# Fans.net
KiCad netlist of a schematic drawn in Altium Designer
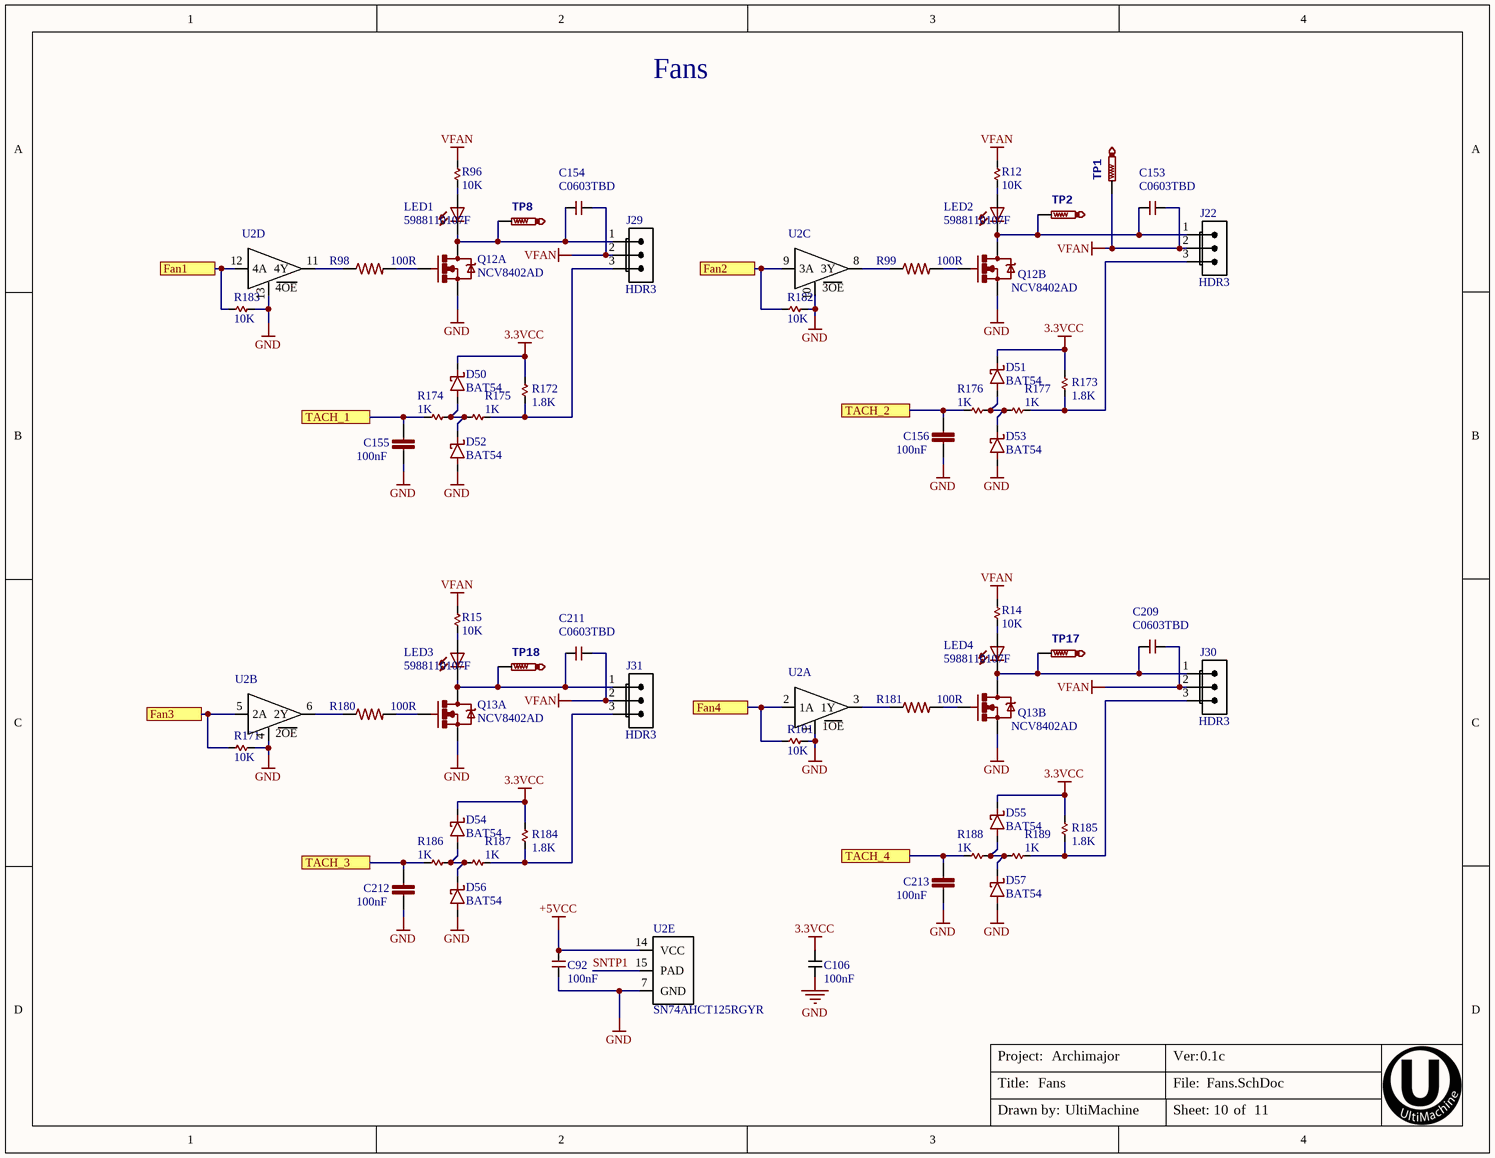
[diagram p0: Fans.SchDoc]

(export (version "E")
  (design (tool "Eeschema 10.0.6"))
  (components
    (comp (ref "C92")
      (value "100nF")
      (footprint "C0402")
      (description "CAP CER 0402 100nF 16V 10% X7R")
      (fields (field (name "MANUFACTURER") "Murata") (field (name "PART") "GRM155R71C104KA88D"))
      (libsource (lib "Capacitors") (part "100nF 0402 16V X7R"))
    )
    (comp (ref "C106")
      (value "100nF")
      (footprint "C0201 Large Pads")
      (description "CAP CER 0.1UF 6.3V 10% X5R 0201")
      (fields (field (name "PART") "CL03A104KQ3NNNC") (field (name "MANUFACTURER") "Samsung"))
      (libsource (lib "Capacitors") (part "100nF 6.3V X5R 0201"))
    )
    (comp (ref "C153")
      (value "C0603TBD")
      (footprint "C0603")
      (description "Capacitor Non Polarized")
      (fields (field (name "PART") "DNI-C0603TBD"))
      (libsource (lib "Capacitors") (part "C0603TBD"))
    )
    (comp (ref "C154")
      (value "C0603TBD")
      (footprint "C0603")
      (description "Capacitor Non Polarized")
      (fields (field (name "PART") "DNI-C0603TBD"))
      (libsource (lib "Capacitors") (part "C0603TBD"))
    )
    (comp (ref "C155")
      (value "100nF")
      (footprint "C0402")
      (description "CAP CER 0402 100nF 16V 10% X7R")
      (fields (field (name "MANUFACTURER") "Murata") (field (name "PART") "GRM155R71C104KA88D"))
      (libsource (lib "3Delight") (part "GRM155R71C104KA88D"))
    )
    (comp (ref "C156")
      (value "100nF")
      (footprint "C0402")
      (description "CAP CER 0402 100nF 16V 10% X7R")
      (fields (field (name "MANUFACTURER") "Murata") (field (name "PART") "GRM155R71C104KA88D"))
      (libsource (lib "3Delight") (part "GRM155R71C104KA88D"))
    )
    (comp (ref "C209")
      (value "C0603TBD")
      (footprint "C0603")
      (description "Capacitor Non Polarized")
      (fields (field (name "PART") "DNI-C0603TBD"))
      (libsource (lib "Capacitors") (part "C0603TBD"))
    )
    (comp (ref "C211")
      (value "C0603TBD")
      (footprint "C0603")
      (description "Capacitor Non Polarized")
      (fields (field (name "PART") "DNI-C0603TBD"))
      (libsource (lib "Capacitors") (part "C0603TBD"))
    )
    (comp (ref "C212")
      (value "100nF")
      (footprint "C0402")
      (description "CAP CER 0402 100nF 16V 10% X7R")
      (fields (field (name "MANUFACTURER") "Murata") (field (name "PART") "GRM155R71C104KA88D"))
      (libsource (lib "3Delight") (part "GRM155R71C104KA88D"))
    )
    (comp (ref "C213")
      (value "100nF")
      (footprint "C0402")
      (description "CAP CER 0402 100nF 16V 10% X7R")
      (fields (field (name "MANUFACTURER") "Murata") (field (name "PART") "GRM155R71C104KA88D"))
      (libsource (lib "3Delight") (part "GRM155R71C104KA88D"))
    )
    (comp (ref "D50")
      (value "BAT54")
      (footprint "SOD523_IPC")
      (description "DIODE SCHOTTKY 30V 200MA SOD523")
      (fields (field (name "MANUFACTURER") "Diodes Incorporated") (field (name "PART") "BAT54WX-TP"))
      (libsource (lib "Diodes") (part "BAT54WX"))
    )
    (comp (ref "D51")
      (value "BAT54")
      (footprint "SOD523_IPC")
      (description "DIODE SCHOTTKY 30V 200MA SOD523")
      (fields (field (name "MANUFACTURER") "Diodes Incorporated") (field (name "PART") "BAT54WX-TP"))
      (libsource (lib "Diodes") (part "BAT54WX"))
    )
    (comp (ref "D52")
      (value "BAT54")
      (footprint "SOD523_IPC")
      (description "DIODE SCHOTTKY 30V 200MA SOD523")
      (fields (field (name "MANUFACTURER") "Diodes Incorporated") (field (name "PART") "BAT54WX-TP"))
      (libsource (lib "Diodes") (part "BAT54WX"))
    )
    (comp (ref "D53")
      (value "BAT54")
      (footprint "SOD523_IPC")
      (description "DIODE SCHOTTKY 30V 200MA SOD523")
      (fields (field (name "MANUFACTURER") "Diodes Incorporated") (field (name "PART") "BAT54WX-TP"))
      (libsource (lib "Diodes") (part "BAT54WX"))
    )
    (comp (ref "D54")
      (value "BAT54")
      (footprint "SOD523_IPC")
      (description "DIODE SCHOTTKY 30V 200MA SOD523")
      (fields (field (name "MANUFACTURER") "Diodes Incorporated") (field (name "PART") "BAT54WX-TP"))
      (libsource (lib "Diodes") (part "BAT54WX"))
    )
    (comp (ref "D55")
      (value "BAT54")
      (footprint "SOD523_IPC")
      (description "DIODE SCHOTTKY 30V 200MA SOD523")
      (fields (field (name "MANUFACTURER") "Diodes Incorporated") (field (name "PART") "BAT54WX-TP"))
      (libsource (lib "Diodes") (part "BAT54WX"))
    )
    (comp (ref "D56")
      (value "BAT54")
      (footprint "SOD523_IPC")
      (description "DIODE SCHOTTKY 30V 200MA SOD523")
      (fields (field (name "MANUFACTURER") "Diodes Incorporated") (field (name "PART") "BAT54WX-TP"))
      (libsource (lib "Diodes") (part "BAT54WX"))
    )
    (comp (ref "D57")
      (value "BAT54")
      (footprint "SOD523_IPC")
      (description "DIODE SCHOTTKY 30V 200MA SOD523")
      (fields (field (name "MANUFACTURER") "Diodes Incorporated") (field (name "PART") "BAT54WX-TP"))
      (libsource (lib "Diodes") (part "BAT54WX"))
    )
    (comp (ref "J22")
      (value "HDR3")
      (footprint "70543-02 PIN-IN-PASTE")
      (description "3 Positions Header, Shrouded Connector 0.100\" (2.54mm) Through Hole Gold - Pin in Paste")
      (fields (field (name "MANUFACTURER") "Molex") (field (name "PART") "0705430002"))
      (libsource (lib "Connectors") (part "CONN 3POS VERT 0.1{dblquote} SHRD LOCKING PIP"))
    )
    (comp (ref "J29")
      (value "HDR3")
      (footprint "70543-02 PIN-IN-PASTE")
      (description "3 Positions Header, Shrouded Connector 0.100\" (2.54mm) Through Hole Gold - Pin in Paste")
      (fields (field (name "MANUFACTURER") "Molex") (field (name "PART") "0705430002"))
      (libsource (lib "Connectors") (part "CONN 3POS VERT 0.1{dblquote} SHRD LOCKING PIP"))
    )
    (comp (ref "J30")
      (value "HDR3")
      (footprint "70543-02 PIN-IN-PASTE")
      (description "3 Positions Header, Shrouded Connector 0.100\" (2.54mm) Through Hole Gold - Pin in Paste")
      (fields (field (name "MANUFACTURER") "Molex") (field (name "PART") "0705430002"))
      (libsource (lib "Connectors") (part "CONN 3POS VERT 0.1{dblquote} SHRD LOCKING PIP"))
    )
    (comp (ref "J31")
      (value "HDR3")
      (footprint "70543-02 PIN-IN-PASTE")
      (description "3 Positions Header, Shrouded Connector 0.100\" (2.54mm) Through Hole Gold - Pin in Paste")
      (fields (field (name "MANUFACTURER") "Molex") (field (name "PART") "0705430002"))
      (libsource (lib "Connectors") (part "CONN 3POS VERT 0.1{dblquote} SHRD LOCKING PIP"))
    )
    (comp (ref "LED1")
      (value "RED")
      (footprint "LED2012120")
      (description "LED 0805 Red")
      (fields
        (field (name "MANUFACTURER") "Dialight")
        (field (name "PART") "5988110107F")
        (field (name "TOLERANCE") "NA")
      )
      (libsource (lib "3Delight") (part "5988110107F"))
    )
    (comp (ref "LED2")
      (value "RED")
      (footprint "LED2012120")
      (description "LED 0805 Red")
      (fields
        (field (name "MANUFACTURER") "Dialight")
        (field (name "PART") "5988110107F")
        (field (name "TOLERANCE") "NA")
      )
      (libsource (lib "3Delight") (part "5988110107F"))
    )
    (comp (ref "LED3")
      (value "RED")
      (footprint "LED2012120")
      (description "LED 0805 Red")
      (fields
        (field (name "MANUFACTURER") "Dialight")
        (field (name "PART") "5988110107F")
        (field (name "TOLERANCE") "NA")
      )
      (libsource (lib "3Delight") (part "5988110107F"))
    )
    (comp (ref "LED4")
      (value "RED")
      (footprint "LED2012120")
      (description "LED 0805 Red")
      (fields
        (field (name "MANUFACTURER") "Dialight")
        (field (name "PART") "5988110107F")
        (field (name "TOLERANCE") "NA")
      )
      (libsource (lib "3Delight") (part "5988110107F"))
    )
    (comp (ref "Q12")
      (value "NCV8402AD")
      (footprint "NCV8402AD-SOIC8")
      (description "IC DVR LOW SIDE 8-SOIC")
      (fields (field (name "MANUFACTURER") "On Semi") (field (name "PART") "NCV8402ADDR2G"))
      (libsource (lib "Transistors") (part "NCV8402AD"))
    )
    (comp (ref "Q13")
      (value "NCV8402AD")
      (footprint "NCV8402AD-SOIC8")
      (description "IC DVR LOW SIDE 8-SOIC")
      (fields (field (name "MANUFACTURER") "On Semi") (field (name "PART") "NCV8402ADDR2G"))
      (libsource (lib "Transistors") (part "NCV8402AD"))
    )
    (comp (ref "R12")
      (value "10K")
      (footprint "R0402")
      (description "RES SMD 10K OHM 1% 1/16W 0402")
      (fields (field (name "MANUFACTURER") "Yageo") (field (name "PART") "RC0402FR-0710KP"))
      (libsource (lib "Resistors") (part "10k 1% 0402"))
    )
    (comp (ref "R14")
      (value "10K")
      (footprint "R0402")
      (description "RES SMD 10K OHM 1% 1/16W 0402")
      (fields (field (name "MANUFACTURER") "Yageo") (field (name "PART") "RC0402FR-0710KP"))
      (libsource (lib "Resistors") (part "10k 1% 0402"))
    )
    (comp (ref "R15")
      (value "10K")
      (footprint "R0402")
      (description "RES SMD 10K OHM 1% 1/16W 0402")
      (fields (field (name "MANUFACTURER") "Yageo") (field (name "PART") "RC0402FR-0710KP"))
      (libsource (lib "Resistors") (part "10k 1% 0402"))
    )
    (comp (ref "R96")
      (value "10K")
      (footprint "R0402")
      (description "RES SMD 10K OHM 1% 1/16W 0402")
      (fields (field (name "MANUFACTURER") "Yageo") (field (name "PART") "RC0402FR-0710KP"))
      (libsource (lib "Resistors") (part "10k 1% 0402"))
    )
    (comp (ref "R98")
      (value "100R")
      (footprint "R0402")
      (description "RES SMD 100 OHM 1% 1/16W 0402")
      (fields (field (name "MANUFACTURER") "Yageo") (field (name "PART") "RC0402FR-07100RL"))
      (libsource (lib "Archim") (part "RES 100R 0402 1%"))
    )
    (comp (ref "R99")
      (value "100R")
      (footprint "R0402")
      (description "RES SMD 100 OHM 1% 1/16W 0402")
      (fields (field (name "MANUFACTURER") "Yageo") (field (name "PART") "RC0402FR-07100RL"))
      (libsource (lib "Archim") (part "RES 100R 0402 1%"))
    )
    (comp (ref "R101")
      (value "10K")
      (footprint "R0402")
      (description "RES SMD 10K OHM 1% 1/16W 0402")
      (fields (field (name "MANUFACTURER") "Yageo") (field (name "PART") "RC0402FR-0710KP"))
      (libsource (lib "Resistors") (part "10k 1% 0402"))
    )
    (comp (ref "R171")
      (value "10K")
      (footprint "R0402")
      (description "RES SMD 10K OHM 1% 1/16W 0402")
      (fields (field (name "MANUFACTURER") "Yageo") (field (name "PART") "RC0402FR-0710KP"))
      (libsource (lib "Resistors") (part "10k 1% 0402"))
    )
    (comp (ref "R172")
      (value "1.8K")
      (footprint "R0402")
      (description "RES SMD 1.8K OHM 1% 1/16W 0402")
      (fields (field (name "MANUFACTURER") "Yageo") (field (name "PART") "RC0402FR-071K8L"))
      (libsource (lib "3Delight") (part "RC0402FR-071K8L"))
    )
    (comp (ref "R173")
      (value "1.8K")
      (footprint "R0402")
      (description "RES SMD 1.8K OHM 1% 1/16W 0402")
      (fields (field (name "MANUFACTURER") "Yageo") (field (name "PART") "RC0402FR-071K8L"))
      (libsource (lib "3Delight") (part "RC0402FR-071K8L"))
    )
    (comp (ref "R174")
      (value "1K")
      (footprint "R0402")
      (description "RES SMD 1K OHM 1% 1/16W 0402")
      (fields (field (name "MANUFACTURER") "Yageo") (field (name "PART") "RC0402FR-071KL"))
      (libsource (lib "3Delight") (part "RC0402FR-071KL"))
    )
    (comp (ref "R175")
      (value "1K")
      (footprint "R0402")
      (description "RES SMD 1K OHM 1% 1/16W 0402")
      (fields (field (name "MANUFACTURER") "Yageo") (field (name "PART") "RC0402FR-071KL"))
      (libsource (lib "3Delight") (part "RC0402FR-071KL"))
    )
    (comp (ref "R176")
      (value "1K")
      (footprint "R0402")
      (description "RES SMD 1K OHM 1% 1/16W 0402")
      (fields (field (name "MANUFACTURER") "Yageo") (field (name "PART") "RC0402FR-071KL"))
      (libsource (lib "3Delight") (part "RC0402FR-071KL"))
    )
    (comp (ref "R177")
      (value "1K")
      (footprint "R0402")
      (description "RES SMD 1K OHM 1% 1/16W 0402")
      (fields (field (name "MANUFACTURER") "Yageo") (field (name "PART") "RC0402FR-071KL"))
      (libsource (lib "3Delight") (part "RC0402FR-071KL"))
    )
    (comp (ref "R180")
      (value "100R")
      (footprint "R0402")
      (description "RES SMD 100 OHM 1% 1/16W 0402")
      (fields (field (name "MANUFACTURER") "Yageo") (field (name "PART") "RC0402FR-07100RL"))
      (libsource (lib "Archim") (part "RES 100R 0402 1%"))
    )
    (comp (ref "R181")
      (value "100R")
      (footprint "R0402")
      (description "RES SMD 100 OHM 1% 1/16W 0402")
      (fields (field (name "MANUFACTURER") "Yageo") (field (name "PART") "RC0402FR-07100RL"))
      (libsource (lib "Archim") (part "RES 100R 0402 1%"))
    )
    (comp (ref "R182")
      (value "10K")
      (footprint "R0402")
      (description "RES SMD 10K OHM 1% 1/16W 0402")
      (fields (field (name "MANUFACTURER") "Yageo") (field (name "PART") "RC0402FR-0710KP"))
      (libsource (lib "Resistors") (part "10k 1% 0402"))
    )
    (comp (ref "R183")
      (value "10K")
      (footprint "R0402")
      (description "RES SMD 10K OHM 1% 1/16W 0402")
      (fields (field (name "MANUFACTURER") "Yageo") (field (name "PART") "RC0402FR-0710KP"))
      (libsource (lib "Resistors") (part "10k 1% 0402"))
    )
    (comp (ref "R184")
      (value "1.8K")
      (footprint "R0402")
      (description "RES SMD 1.8K OHM 1% 1/16W 0402")
      (fields (field (name "MANUFACTURER") "Yageo") (field (name "PART") "RC0402FR-071K8L"))
      (libsource (lib "3Delight") (part "RC0402FR-071K8L"))
    )
    (comp (ref "R185")
      (value "1.8K")
      (footprint "R0402")
      (description "RES SMD 1.8K OHM 1% 1/16W 0402")
      (fields (field (name "MANUFACTURER") "Yageo") (field (name "PART") "RC0402FR-071K8L"))
      (libsource (lib "3Delight") (part "RC0402FR-071K8L"))
    )
    (comp (ref "R186")
      (value "1K")
      (footprint "R0402")
      (description "RES SMD 1K OHM 1% 1/16W 0402")
      (fields (field (name "MANUFACTURER") "Yageo") (field (name "PART") "RC0402FR-071KL"))
      (libsource (lib "3Delight") (part "RC0402FR-071KL"))
    )
    (comp (ref "R187")
      (value "1K")
      (footprint "R0402")
      (description "RES SMD 1K OHM 1% 1/16W 0402")
      (fields (field (name "MANUFACTURER") "Yageo") (field (name "PART") "RC0402FR-071KL"))
      (libsource (lib "3Delight") (part "RC0402FR-071KL"))
    )
    (comp (ref "R188")
      (value "1K")
      (footprint "R0402")
      (description "RES SMD 1K OHM 1% 1/16W 0402")
      (fields (field (name "MANUFACTURER") "Yageo") (field (name "PART") "RC0402FR-071KL"))
      (libsource (lib "3Delight") (part "RC0402FR-071KL"))
    )
    (comp (ref "R189")
      (value "1K")
      (footprint "R0402")
      (description "RES SMD 1K OHM 1% 1/16W 0402")
      (fields (field (name "MANUFACTURER") "Yageo") (field (name "PART") "RC0402FR-071KL"))
      (libsource (lib "3Delight") (part "RC0402FR-071KL"))
    )
    (comp (ref "TP1")
      (value "TestPoint")
      (footprint "TP1-27")
      (description "Test Point")
      (libsource (lib "") (part "TestPoint_1"))
    )
    (comp (ref "TP2")
      (value "TestPoint")
      (footprint "TP1-27")
      (description "Test Point")
      (libsource (lib "3Delight") (part "TestPoint"))
    )
    (comp (ref "TP8")
      (value "TestPoint")
      (footprint "TP1-27")
      (description "Test Point")
      (libsource (lib "3Delight") (part "TestPoint"))
    )
    (comp (ref "TP17")
      (value "TestPoint")
      (footprint "TP1-27")
      (description "Test Point")
      (libsource (lib "3Delight") (part "TestPoint"))
    )
    (comp (ref "TP18")
      (value "TestPoint")
      (footprint "TP1-27")
      (description "Test Point")
      (libsource (lib "3Delight") (part "TestPoint"))
    )
    (comp (ref "U2")
      (value "SN74AHCT125RGYR")
      (footprint "QFN50P350X350X100_RGY_S-PVQFN-N14")
      (description "Quadruple Bus Buffer Gates With 3-State Outputs 14-VQFN -40 to 125")
      (fields (field (name "MANUFACTURER") "Texas Instruments") (field (name "TOLERANCE") "-NA-"))
      (libsource (lib "ICs-Logic") (part "SN74AHCT125"))
    )
  )
  (nets
    (net (code "1") (name "+5VCC") (class "Default")
      (node (ref "C92") (pin "2") (pinfunction "2_2") (pintype "passive"))
      (node (ref "U2") (pin "14") (pinfunction "VCC_14") (pintype "passive"))
    )
    (net (code "2") (name "/Fan1") (class "Default")
      (node (ref "R183") (pin "1") (pinfunction "1_1") (pintype "passive"))
      (node (ref "U2") (pin "12") (pinfunction "4A_12") (pintype "passive"))
    )
    (net (code "3") (name "/Fan2") (class "Default")
      (node (ref "R182") (pin "1") (pinfunction "1_1") (pintype "passive"))
      (node (ref "U2") (pin "9") (pinfunction "3A_9") (pintype "passive"))
    )
    (net (code "4") (name "/Fan3") (class "Default")
      (node (ref "R171") (pin "1") (pinfunction "1_1") (pintype "passive"))
      (node (ref "U2") (pin "5") (pinfunction "2A_5") (pintype "passive"))
    )
    (net (code "5") (name "/Fan4") (class "Default")
      (node (ref "R101") (pin "1") (pinfunction "1_1") (pintype "passive"))
      (node (ref "U2") (pin "2") (pinfunction "1A_2") (pintype "passive"))
    )
    (net (code "6") (name "/SNTP1") (class "Default")
      (node (ref "U2") (pin "15") (pinfunction "PAD_15") (pintype "passive"))
    )
    (net (code "7") (name "/TACH_1") (class "Default")
      (node (ref "C155") (pin "1") (pinfunction "1_1") (pintype "passive"))
      (node (ref "R174") (pin "1") (pinfunction "1_1") (pintype "passive"))
    )
    (net (code "8") (name "/TACH_2") (class "Default")
      (node (ref "C156") (pin "1") (pinfunction "1_1") (pintype "passive"))
      (node (ref "R176") (pin "1") (pinfunction "1_1") (pintype "passive"))
    )
    (net (code "9") (name "/TACH_3") (class "Default")
      (node (ref "C212") (pin "1") (pinfunction "1_1") (pintype "passive"))
      (node (ref "R186") (pin "1") (pinfunction "1_1") (pintype "passive"))
    )
    (net (code "10") (name "/TACH_4") (class "Default")
      (node (ref "C213") (pin "1") (pinfunction "1_1") (pintype "passive"))
      (node (ref "R188") (pin "1") (pinfunction "1_1") (pintype "passive"))
    )
    (net (code "11") (name "3.3VCC") (class "Default")
      (node (ref "C106") (pin "2") (pinfunction "2_2") (pintype "passive"))
      (node (ref "D50") (pin "K") (pinfunction "K_K") (pintype "passive"))
      (node (ref "D51") (pin "K") (pinfunction "K_K") (pintype "passive"))
      (node (ref "D54") (pin "K") (pinfunction "K_K") (pintype "passive"))
      (node (ref "D55") (pin "K") (pinfunction "K_K") (pintype "passive"))
      (node (ref "R172") (pin "2") (pinfunction "2_2") (pintype "passive"))
      (node (ref "R173") (pin "2") (pinfunction "2_2") (pintype "passive"))
      (node (ref "R184") (pin "2") (pinfunction "2_2") (pintype "passive"))
      (node (ref "R185") (pin "2") (pinfunction "2_2") (pintype "passive"))
    )
    (net (code "12") (name "GND") (class "Default")
      (node (ref "C106") (pin "1") (pinfunction "1_1") (pintype "passive"))
      (node (ref "C155") (pin "2") (pinfunction "2_2") (pintype "passive"))
      (node (ref "C156") (pin "2") (pinfunction "2_2") (pintype "passive"))
      (node (ref "C212") (pin "2") (pinfunction "2_2") (pintype "passive"))
      (node (ref "C213") (pin "2") (pinfunction "2_2") (pintype "passive"))
      (node (ref "C92") (pin "1") (pinfunction "1_1") (pintype "passive"))
      (node (ref "D52") (pin "A") (pinfunction "A_A") (pintype "passive"))
      (node (ref "D56") (pin "A") (pinfunction "A_A") (pintype "passive"))
      (node (ref "D57") (pin "A") (pinfunction "A_A") (pintype "passive"))
      (node (ref "Q12") (pin "1") (pinfunction "S_1") (pintype "passive"))
      (node (ref "Q12") (pin "3") (pinfunction "S_3") (pintype "passive"))
      (node (ref "Q13") (pin "1") (pinfunction "S_1") (pintype "passive"))
      (node (ref "Q13") (pin "3") (pinfunction "S_3") (pintype "passive"))
      (node (ref "R101") (pin "2") (pinfunction "2_2") (pintype "passive"))
      (node (ref "R171") (pin "2") (pinfunction "2_2") (pintype "passive"))
      (node (ref "R182") (pin "2") (pinfunction "2_2") (pintype "passive"))
      (node (ref "R183") (pin "2") (pinfunction "2_2") (pintype "passive"))
      (node (ref "U2") (pin "1") (pinfunction "1OE_1") (pintype "passive"))
      (node (ref "U2") (pin "10") (pinfunction "3OE_10") (pintype "passive"))
      (node (ref "U2") (pin "13") (pinfunction "4OE_13") (pintype "passive"))
      (node (ref "U2") (pin "4") (pinfunction "2OE_4") (pintype "passive"))
      (node (ref "U2") (pin "7") (pinfunction "GND_7") (pintype "passive"))
    )
    (net (code "13") (name "Net-(D50-PadA)") (class "Default")
      (node (ref "D50") (pin "A") (pinfunction "A_A") (pintype "passive"))
      (node (ref "D52") (pin "K") (pinfunction "K_K") (pintype "passive"))
      (node (ref "R174") (pin "2") (pinfunction "2_2") (pintype "passive"))
      (node (ref "R175") (pin "1") (pinfunction "1_1") (pintype "passive"))
    )
    (net (code "14") (name "Net-(D51-PadA)") (class "Default")
      (node (ref "D51") (pin "A") (pinfunction "A_A") (pintype "passive"))
      (node (ref "D53") (pin "K") (pinfunction "K_K") (pintype "passive"))
      (node (ref "R176") (pin "2") (pinfunction "2_2") (pintype "passive"))
      (node (ref "R177") (pin "1") (pinfunction "1_1") (pintype "passive"))
    )
    (net (code "15") (name "Net-(D54-PadA)") (class "Default")
      (node (ref "D54") (pin "A") (pinfunction "A_A") (pintype "passive"))
      (node (ref "D56") (pin "K") (pinfunction "K_K") (pintype "passive"))
      (node (ref "R186") (pin "2") (pinfunction "2_2") (pintype "passive"))
      (node (ref "R187") (pin "1") (pinfunction "1_1") (pintype "passive"))
    )
    (net (code "16") (name "Net-(D55-PadA)") (class "Default")
      (node (ref "D55") (pin "A") (pinfunction "A_A") (pintype "passive"))
      (node (ref "D57") (pin "K") (pinfunction "K_K") (pintype "passive"))
      (node (ref "R188") (pin "2") (pinfunction "2_2") (pintype "passive"))
      (node (ref "R189") (pin "1") (pinfunction "1_1") (pintype "passive"))
    )
    (net (code "17") (name "Net-(J22-S-Pad3)") (class "Default")
      (node (ref "J22") (pin "3") (pinfunction "S_3") (pintype "passive"))
      (node (ref "R173") (pin "1") (pinfunction "1_1") (pintype "passive"))
      (node (ref "R177") (pin "2") (pinfunction "2_2") (pintype "passive"))
    )
    (net (code "18") (name "Net-(J29-S-Pad3)") (class "Default")
      (node (ref "J29") (pin "3") (pinfunction "S_3") (pintype "passive"))
      (node (ref "R172") (pin "1") (pinfunction "1_1") (pintype "passive"))
      (node (ref "R175") (pin "2") (pinfunction "2_2") (pintype "passive"))
    )
    (net (code "19") (name "Net-(J30-S-Pad3)") (class "Default")
      (node (ref "J30") (pin "3") (pinfunction "S_3") (pintype "passive"))
      (node (ref "R185") (pin "1") (pinfunction "1_1") (pintype "passive"))
      (node (ref "R189") (pin "2") (pinfunction "2_2") (pintype "passive"))
    )
    (net (code "20") (name "Net-(J31-S-Pad3)") (class "Default")
      (node (ref "J31") (pin "3") (pinfunction "S_3") (pintype "passive"))
      (node (ref "R184") (pin "1") (pinfunction "1_1") (pintype "passive"))
      (node (ref "R187") (pin "2") (pinfunction "2_2") (pintype "passive"))
    )
    (net (code "21") (name "Net-(LED1-PadA)") (class "Default")
      (node (ref "LED1") (pin "A") (pinfunction "A_A") (pintype "passive"))
      (node (ref "R96") (pin "1") (pinfunction "1_1") (pintype "passive"))
    )
    (net (code "22") (name "Net-(LED2-PadA)") (class "Default")
      (node (ref "LED2") (pin "A") (pinfunction "A_A") (pintype "passive"))
      (node (ref "R12") (pin "1") (pinfunction "1_1") (pintype "passive"))
    )
    (net (code "23") (name "Net-(LED3-PadA)") (class "Default")
      (node (ref "LED3") (pin "A") (pinfunction "A_A") (pintype "passive"))
      (node (ref "R15") (pin "1") (pinfunction "1_1") (pintype "passive"))
    )
    (net (code "24") (name "Net-(LED4-PadA)") (class "Default")
      (node (ref "LED4") (pin "A") (pinfunction "A_A") (pintype "passive"))
      (node (ref "R14") (pin "1") (pinfunction "1_1") (pintype "passive"))
    )
    (net (code "25") (name "Net-(Q12A-D)") (class "Default")
      (node (ref "C154") (pin "2") (pinfunction "2_2") (pintype "passive"))
      (node (ref "J29") (pin "1") (pinfunction "S_1") (pintype "passive"))
      (node (ref "LED1") (pin "C") (pinfunction "C_C") (pintype "passive"))
      (node (ref "Q12") (pin "7") (pinfunction "D_7") (pintype "passive"))
      (node (ref "TP8") (pin "TP") (pinfunction "TP_TP") (pintype "passive"))
    )
    (net (code "26") (name "Net-(Q12A-G)") (class "Default")
      (node (ref "Q12") (pin "2") (pinfunction "G_2") (pintype "passive"))
      (node (ref "R98") (pin "2") (pinfunction "2_2") (pintype "passive"))
    )
    (net (code "27") (name "Net-(Q12B-D)") (class "Default")
      (node (ref "C153") (pin "2") (pinfunction "2_2") (pintype "passive"))
      (node (ref "J22") (pin "1") (pinfunction "S_1") (pintype "passive"))
      (node (ref "LED2") (pin "C") (pinfunction "C_C") (pintype "passive"))
      (node (ref "Q12") (pin "5") (pinfunction "D_5") (pintype "passive"))
      (node (ref "TP2") (pin "TP") (pinfunction "TP_TP") (pintype "passive"))
    )
    (net (code "28") (name "Net-(Q12B-G)") (class "Default")
      (node (ref "Q12") (pin "4") (pinfunction "G_4") (pintype "passive"))
      (node (ref "R99") (pin "2") (pinfunction "2_2") (pintype "passive"))
    )
    (net (code "29") (name "Net-(Q13A-D)") (class "Default")
      (node (ref "C211") (pin "2") (pinfunction "2_2") (pintype "passive"))
      (node (ref "J31") (pin "1") (pinfunction "S_1") (pintype "passive"))
      (node (ref "LED3") (pin "C") (pinfunction "C_C") (pintype "passive"))
      (node (ref "Q13") (pin "7") (pinfunction "D_7") (pintype "passive"))
      (node (ref "TP18") (pin "TP") (pinfunction "TP_TP") (pintype "passive"))
    )
    (net (code "30") (name "Net-(Q13A-G)") (class "Default")
      (node (ref "Q13") (pin "2") (pinfunction "G_2") (pintype "passive"))
      (node (ref "R180") (pin "2") (pinfunction "2_2") (pintype "passive"))
    )
    (net (code "31") (name "Net-(Q13B-D)") (class "Default")
      (node (ref "C209") (pin "2") (pinfunction "2_2") (pintype "passive"))
      (node (ref "J30") (pin "1") (pinfunction "S_1") (pintype "passive"))
      (node (ref "LED4") (pin "C") (pinfunction "C_C") (pintype "passive"))
      (node (ref "Q13") (pin "5") (pinfunction "D_5") (pintype "passive"))
      (node (ref "TP17") (pin "TP") (pinfunction "TP_TP") (pintype "passive"))
    )
    (net (code "32") (name "Net-(Q13B-G)") (class "Default")
      (node (ref "Q13") (pin "4") (pinfunction "G_4") (pintype "passive"))
      (node (ref "R181") (pin "2") (pinfunction "2_2") (pintype "passive"))
    )
    (net (code "33") (name "Net-(U2A-1Y)") (class "Default")
      (node (ref "R181") (pin "1") (pinfunction "1_1") (pintype "passive"))
      (node (ref "U2") (pin "3") (pinfunction "1Y_3") (pintype "passive"))
    )
    (net (code "34") (name "Net-(U2B-2Y)") (class "Default")
      (node (ref "R180") (pin "1") (pinfunction "1_1") (pintype "passive"))
      (node (ref "U2") (pin "6") (pinfunction "2Y_6") (pintype "passive"))
    )
    (net (code "35") (name "Net-(U2C-3Y)") (class "Default")
      (node (ref "R99") (pin "1") (pinfunction "1_1") (pintype "passive"))
      (node (ref "U2") (pin "8") (pinfunction "3Y_8") (pintype "passive"))
    )
    (net (code "36") (name "Net-(U2D-4Y)") (class "Default")
      (node (ref "R98") (pin "1") (pinfunction "1_1") (pintype "passive"))
      (node (ref "U2") (pin "11") (pinfunction "4Y_11") (pintype "passive"))
    )
    (net (code "37") (name "VFAN") (class "Default")
      (node (ref "C153") (pin "1") (pinfunction "1_1") (pintype "passive"))
      (node (ref "C154") (pin "1") (pinfunction "1_1") (pintype "passive"))
      (node (ref "C209") (pin "1") (pinfunction "1_1") (pintype "passive"))
      (node (ref "C211") (pin "1") (pinfunction "1_1") (pintype "passive"))
      (node (ref "J22") (pin "2") (pinfunction "S_2") (pintype "passive"))
      (node (ref "J29") (pin "2") (pinfunction "S_2") (pintype "passive"))
      (node (ref "J30") (pin "2") (pinfunction "S_2") (pintype "passive"))
      (node (ref "J31") (pin "2") (pinfunction "S_2") (pintype "passive"))
      (node (ref "R12") (pin "2") (pinfunction "2_2") (pintype "passive"))
      (node (ref "R14") (pin "2") (pinfunction "2_2") (pintype "passive"))
      (node (ref "R15") (pin "2") (pinfunction "2_2") (pintype "passive"))
      (node (ref "R96") (pin "2") (pinfunction "2_2") (pintype "passive"))
      (node (ref "TP1") (pin "TP") (pinfunction "TP_TP") (pintype "passive"))
    )
    (net (code "38") (name "unconnected-(D53-PadA)") (class "Default")
      (node (ref "D53") (pin "A") (pinfunction "A_A") (pintype "passive"))
    )
  )
)
